# relays.net
KiCad netlist of a schematic drawn in EAGLE
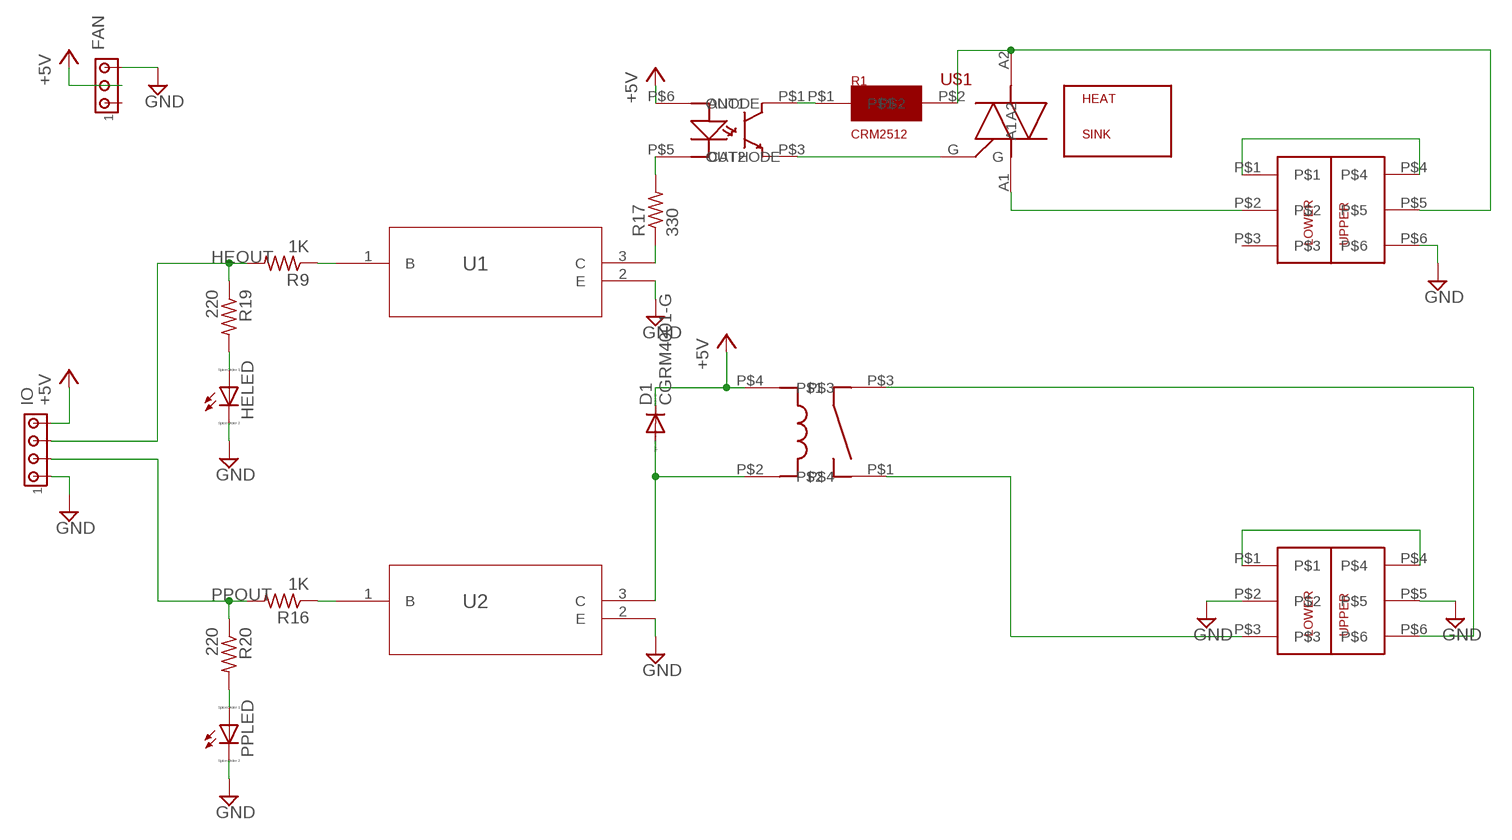
[diagram p0: schematic, sheet 1]

(export (version "E")
  (design (tool "Eeschema 10.0.6"))
  (components
    (comp (ref "D1")
      (value "CGRM4001-G")
      (footprint "eagle-import:SOD-123_MINI-SMA")
      (libsource (lib "eagle-import") (part "CGRM400-G1"))
    )
    (comp (ref "FAN")
      (value "MTA03-100")
      (footprint "eagle-import:10X03MTA")
      (libsource (lib "eagle-import") (part "MTA03-100"))
    )
    (comp (ref "HELED")
      (value "LED_ESML0603")
      (footprint "eagle-import:LED_SML0603")
      (libsource (lib "eagle-import") (part "LED_ESML0603"))
    )
    (comp (ref "IO")
      (value "MTA04-100")
      (footprint "eagle-import:10X04MTA")
      (libsource (lib "eagle-import") (part "MTA04-100"))
    )
    (comp (ref "PPLED")
      (value "LED_ESML0603")
      (footprint "eagle-import:LED_SML0603")
      (libsource (lib "eagle-import") (part "LED_ESML0603"))
    )
    (comp (ref "R1")
      (value "CRM2512")
      (footprint "eagle-import:2512(6432METRIC)")
      (libsource (lib "eagle-import") (part "CRM2512"))
    )
    (comp (ref "R9")
      (value "1K")
      (footprint "eagle-import:R0402")
      (libsource (lib "eagle-import") (part "resistor_348_R-US_R0402"))
    )
    (comp (ref "R16")
      (value "1K")
      (footprint "eagle-import:R0402")
      (libsource (lib "eagle-import") (part "resistor_348_R-US_R0402"))
    )
    (comp (ref "R17")
      (value "330")
      (footprint "eagle-import:R1206")
      (libsource (lib "eagle-import") (part "resistor_348_R-US_R1206"))
    )
    (comp (ref "R19")
      (value "220")
      (footprint "eagle-import:R0402")
      (libsource (lib "eagle-import") (part "R-US_R0402"))
    )
    (comp (ref "R20")
      (value "220")
      (footprint "eagle-import:R0402")
      (libsource (lib "eagle-import") (part "R-US_R0402"))
    )
    (comp (ref "U$1")
      (value "T3050H-6I")
      (footprint "eagle-import:TO-220")
      (libsource (lib "eagle-import") (part "T3050H-6I"))
    )
    (comp (ref "U$2")
      (value "VM1-038-1AEHORIZONTAL")
      (footprint "eagle-import:VM2-038-1AE")
      (libsource (lib "eagle-import") (part "VM1-038-1AEHORIZONTAL"))
    )
    (comp (ref "U$3")
      (value "G5LE-1A4_DC5")
      (footprint "eagle-import:G5LE-1A4_DC5")
      (libsource (lib "eagle-import") (part "G5LE-1A4_DC5"))
    )
    (comp (ref "U$4")
      (value "PC1725041")
      (footprint "eagle-import:PC-MKKDS1.5_3-5.08")
      (libsource (lib "eagle-import") (part "PC1725041"))
    )
    (comp (ref "U$5")
      (value "MOC3020S")
      (footprint "eagle-import:6-SMD")
      (libsource (lib "eagle-import") (part "MOC3020S"))
    )
    (comp (ref "U$6")
      (value "PC1719028")
      (footprint "eagle-import:PC-MKKDS5_3-9.5")
      (libsource (lib "eagle-import") (part "PC1719028"))
    )
    (comp (ref "U1")
      (value "MMBT2222ALT1G")
      (footprint "eagle-import:SOT-23")
      (libsource (lib "eagle-import") (part "MMBT2222ALT1G"))
    )
    (comp (ref "U2")
      (value "MMBT2222ALT1G")
      (footprint "eagle-import:SOT-23")
      (libsource (lib "eagle-import") (part "MMBT2222ALT1G"))
    )
  )
  (nets
    (net (code "1") (name "+5V") (class "Default")
      (node (ref "D1") (pin "C") (pinfunction "C_C") (pintype "passive"))
      (node (ref "FAN") (pin "2") (pinfunction "2_2") (pintype "passive"))
      (node (ref "IO") (pin "4") (pinfunction "4_4") (pintype "passive"))
      (node (ref "U$3") (pin "P$4") (pinfunction "P$1_P$4") (pintype "bidirectional"))
      (node (ref "U$5") (pin "P$6") (pinfunction "ANODE_P$6") (pintype "bidirectional"))
    )
    (net (code "2") (name "/HEOUT") (class "Default")
      (node (ref "IO") (pin "3") (pinfunction "3_3") (pintype "passive"))
      (node (ref "R19") (pin "1") (pinfunction "1_1") (pintype "passive"))
      (node (ref "R9") (pin "2") (pinfunction "2_2") (pintype "passive"))
    )
    (net (code "3") (name "/PPOUT") (class "Default")
      (node (ref "IO") (pin "2") (pinfunction "2_2") (pintype "passive"))
      (node (ref "R16") (pin "2") (pinfunction "2_2") (pintype "passive"))
      (node (ref "R20") (pin "1") (pinfunction "1_1") (pintype "passive"))
    )
    (net (code "4") (name "GND") (class "Default")
      (node (ref "FAN") (pin "3") (pinfunction "3_3") (pintype "passive"))
      (node (ref "HELED") (pin "C") (pinfunction "C_C") (pintype "passive"))
      (node (ref "IO") (pin "1") (pinfunction "1_1") (pintype "passive"))
      (node (ref "PPLED") (pin "C") (pinfunction "C_C") (pintype "passive"))
      (node (ref "U$4") (pin "P$2") (pinfunction "P$2_P$2") (pintype "bidirectional"))
      (node (ref "U$4") (pin "P$5") (pinfunction "P$5_P$5") (pintype "bidirectional"))
      (node (ref "U$6") (pin "P$6") (pinfunction "P$6_P$6") (pintype "bidirectional"))
      (node (ref "U1") (pin "2") (pinfunction "E_2") (pintype "passive"))
      (node (ref "U2") (pin "2") (pinfunction "E_2") (pintype "passive"))
    )
    (net (code "5") (name "Net-(HELED-PadA)") (class "Default")
      (node (ref "HELED") (pin "A") (pinfunction "A_A") (pintype "passive"))
      (node (ref "R19") (pin "2") (pinfunction "2_2") (pintype "passive"))
    )
    (net (code "6") (name "Net-(PPLED-PadA)") (class "Default")
      (node (ref "PPLED") (pin "A") (pinfunction "A_A") (pintype "passive"))
      (node (ref "R20") (pin "2") (pinfunction "2_2") (pintype "passive"))
    )
    (net (code "7") (name "Net-(R1-PadP$2)") (class "Default")
      (node (ref "R1") (pin "P$2") (pinfunction "P$2_P$2") (pintype "bidirectional"))
      (node (ref "U$1") (pin "A2") (pinfunction "A2_A2") (pintype "bidirectional"))
      (node (ref "U$6") (pin "P$5") (pinfunction "P$5_P$5") (pintype "bidirectional"))
    )
    (net (code "8") (name "Net-(U$1-PadA1)") (class "Default")
      (node (ref "U$1") (pin "A1") (pinfunction "A1_A1") (pintype "bidirectional"))
      (node (ref "U$6") (pin "P$2") (pinfunction "P$2_P$2") (pintype "bidirectional"))
    )
    (net (code "9") (name "Net-(U$3-P$4)") (class "Default")
      (node (ref "U$3") (pin "P$1") (pinfunction "P$4_P$1") (pintype "bidirectional"))
      (node (ref "U$4") (pin "P$3") (pinfunction "P$3_P$3") (pintype "bidirectional"))
    )
    (net (code "10") (name "Net-(U$3-PadP$3)") (class "Default")
      (node (ref "U$3") (pin "P$3") (pinfunction "P$3_P$3") (pintype "bidirectional"))
      (node (ref "U$4") (pin "P$6") (pinfunction "P$6_P$6") (pintype "bidirectional"))
    )
    (net (code "11") (name "Net-(U$4-PadP$1)") (class "Default")
      (node (ref "U$4") (pin "P$1") (pinfunction "P$1_P$1") (pintype "bidirectional"))
      (node (ref "U$4") (pin "P$4") (pinfunction "P$4_P$4") (pintype "bidirectional"))
    )
    (net (code "12") (name "Net-(U$5-CATHODE)") (class "Default")
      (node (ref "R17") (pin "2") (pinfunction "2_2") (pintype "passive"))
      (node (ref "U$5") (pin "P$5") (pinfunction "CATHODE_P$5") (pintype "bidirectional"))
    )
    (net (code "13") (name "Net-(U$5-OUT1)") (class "Default")
      (node (ref "R1") (pin "P$1") (pinfunction "P$1_P$1") (pintype "bidirectional"))
      (node (ref "U$5") (pin "P$1") (pinfunction "OUT1_P$1") (pintype "bidirectional"))
    )
    (net (code "14") (name "Net-(U$5-OUT2)") (class "Default")
      (node (ref "U$1") (pin "G") (pinfunction "G_G") (pintype "bidirectional"))
      (node (ref "U$5") (pin "P$3") (pinfunction "OUT2_P$3") (pintype "bidirectional"))
    )
    (net (code "15") (name "Net-(U$6-PadP$1)") (class "Default")
      (node (ref "U$6") (pin "P$1") (pinfunction "P$1_P$1") (pintype "bidirectional"))
      (node (ref "U$6") (pin "P$4") (pinfunction "P$4_P$4") (pintype "bidirectional"))
    )
    (net (code "16") (name "Net-(U1-B)") (class "Default")
      (node (ref "R9") (pin "1") (pinfunction "1_1") (pintype "passive"))
      (node (ref "U1") (pin "1") (pinfunction "B_1") (pintype "passive"))
    )
    (net (code "17") (name "Net-(U1-C)") (class "Default")
      (node (ref "R17") (pin "1") (pinfunction "1_1") (pintype "passive"))
      (node (ref "U1") (pin "3") (pinfunction "C_3") (pintype "passive"))
    )
    (net (code "18") (name "Net-(U2-B)") (class "Default")
      (node (ref "R16") (pin "1") (pinfunction "1_1") (pintype "passive"))
      (node (ref "U2") (pin "1") (pinfunction "B_1") (pintype "passive"))
    )
    (net (code "19") (name "Net-(U2-C)") (class "Default")
      (node (ref "D1") (pin "A") (pinfunction "A_A") (pintype "passive"))
      (node (ref "U$3") (pin "P$2") (pinfunction "P$2_P$2") (pintype "bidirectional"))
      (node (ref "U2") (pin "3") (pinfunction "C_3") (pintype "passive"))
    )
    (net (code "20") (name "unconnected-(FAN-Pad1)") (class "Default")
      (node (ref "FAN") (pin "1") (pinfunction "1_1") (pintype "passive"))
    )
    (net (code "21") (name "unconnected-(U$6-PadP$3)") (class "Default")
      (node (ref "U$6") (pin "P$3") (pinfunction "P$3_P$3") (pintype "bidirectional"))
    )
  )
)
